# Sch3.net
KiCad netlist of a schematic drawn in Altium Designer
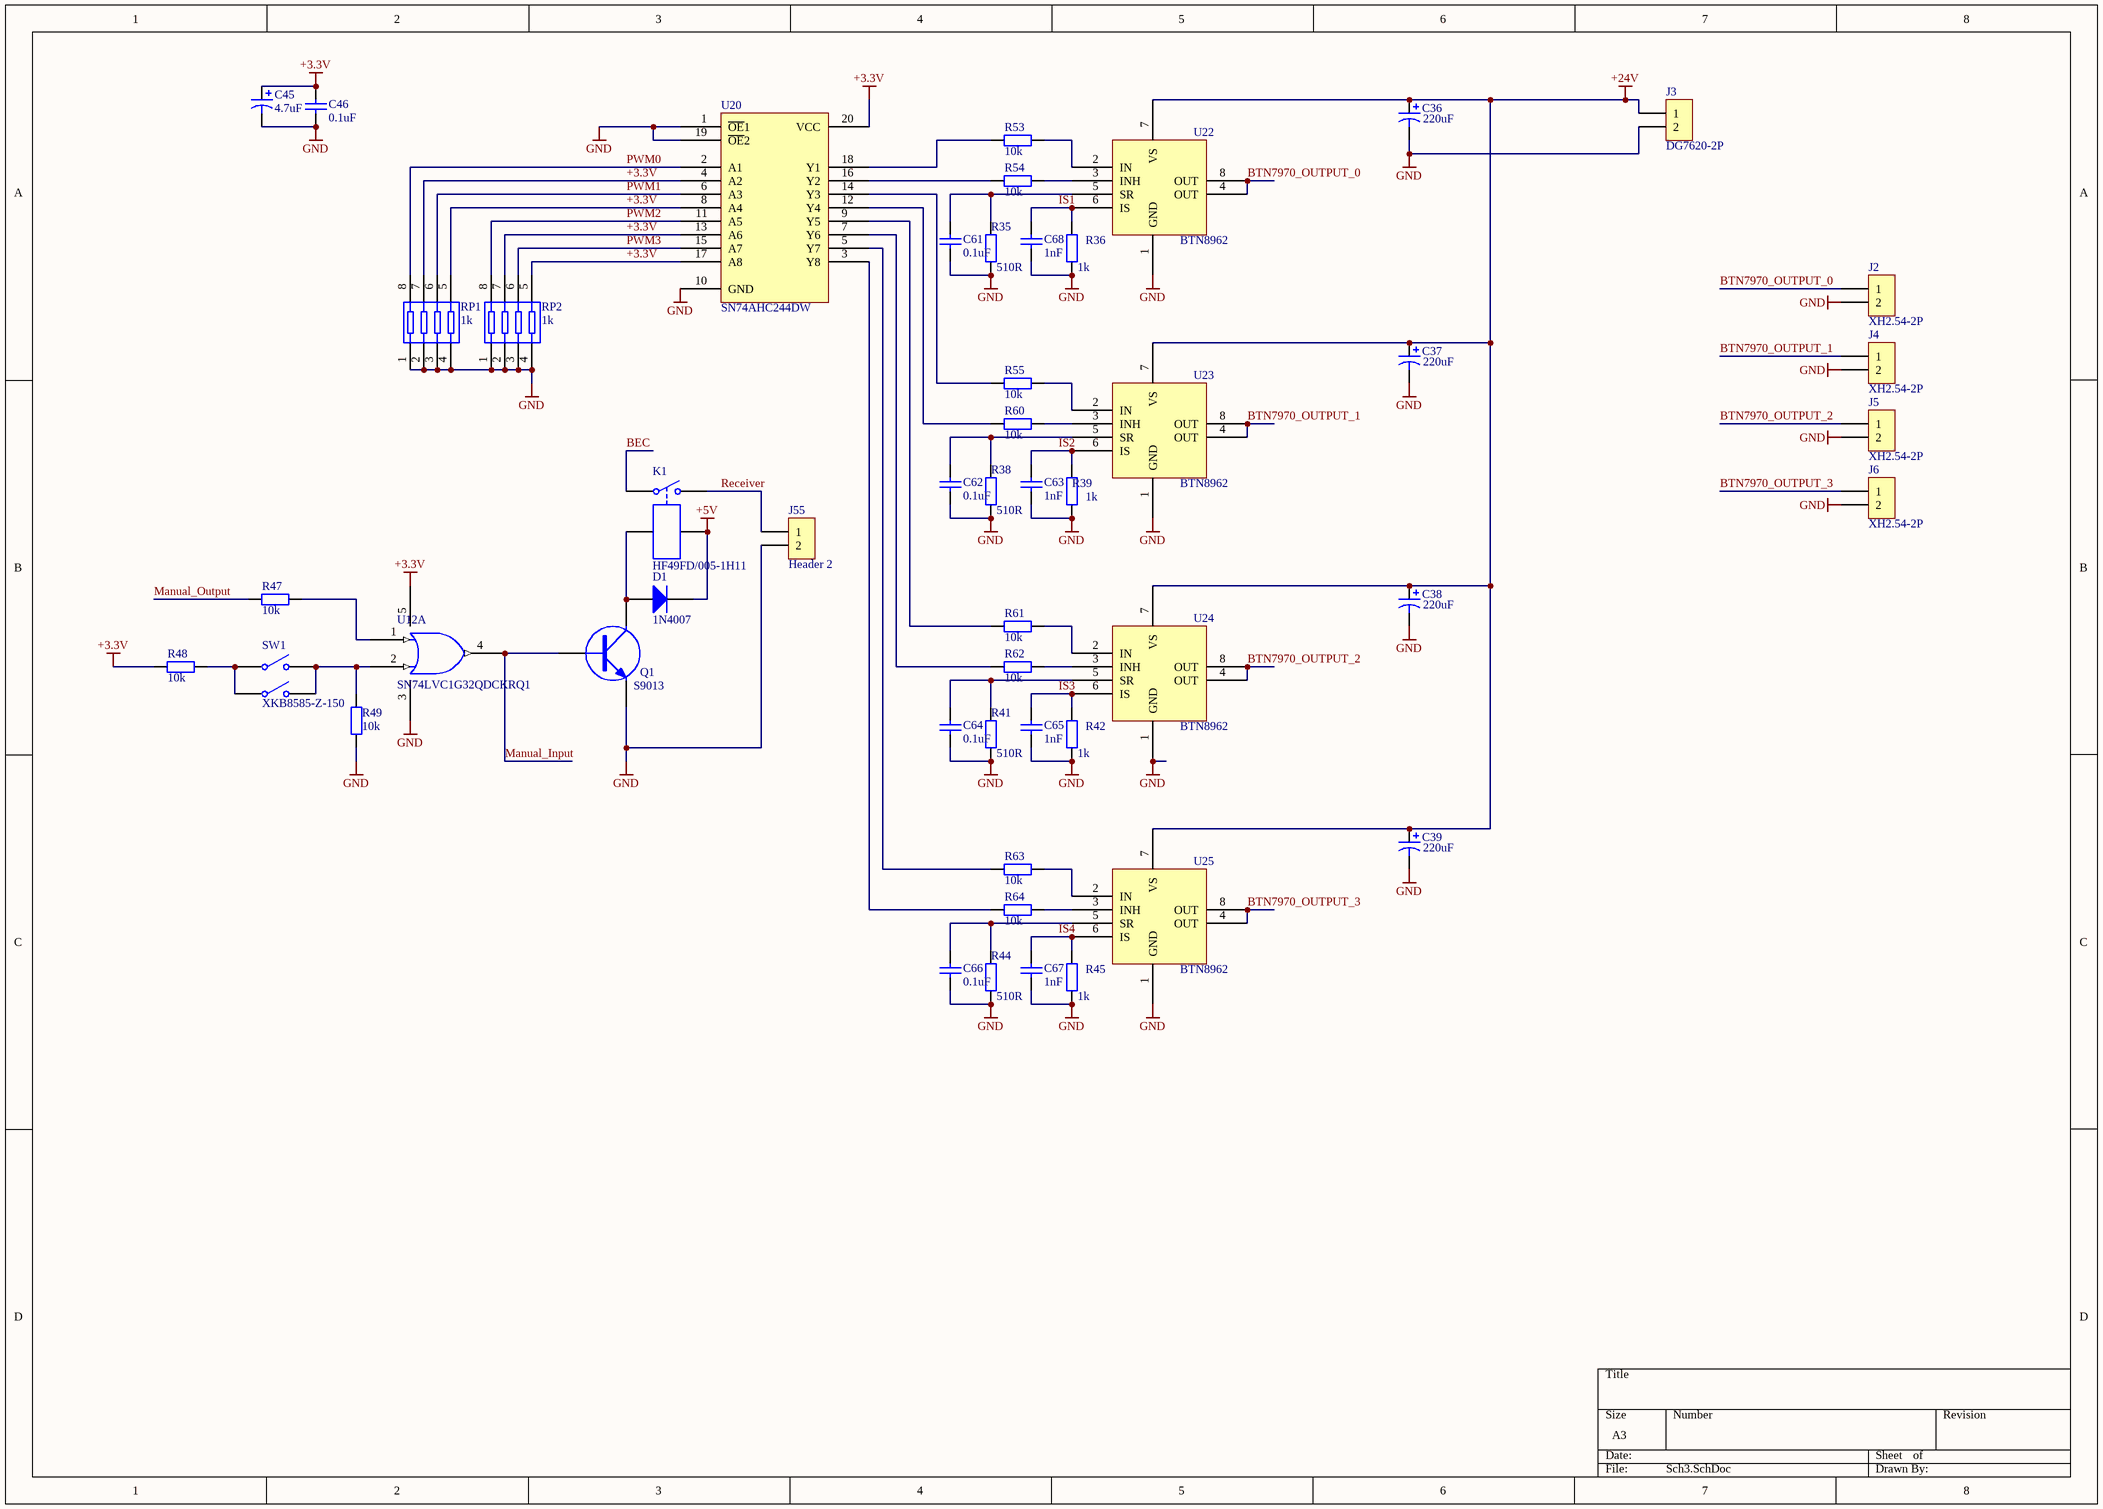
[diagram p0: Sch3.SchDoc]

(export (version "E")
  (design (tool "Eeschema 10.0.6"))
  (components
    (comp (ref "C36")
      (value "220uF")
      (footprint "SMD-EC-F8")
      (description "贴片铝电解电容")
      (fields (field (name "Comment") "CD-50V-220uF-F8(SMD)"))
      (libsource (lib "Miscellaneous Devices") (part "Cap Pol3"))
    )
    (comp (ref "C37")
      (value "220uF")
      (footprint "SMD-EC-F8")
      (description "贴片铝电解电容")
      (fields (field (name "Comment") "CD-50V-220uF-F8(SMD)"))
      (libsource (lib "Miscellaneous Devices") (part "Cap Pol3"))
    )
    (comp (ref "C38")
      (value "220uF")
      (footprint "SMD-EC-F8")
      (description "贴片铝电解电容")
      (fields (field (name "Comment") "CD-50V-220uF-F8(SMD)"))
      (libsource (lib "Miscellaneous Devices") (part "Cap Pol3"))
    )
    (comp (ref "C39")
      (value "220uF")
      (footprint "SMD-EC-F8")
      (description "贴片铝电解电容")
      (fields (field (name "Comment") "CD-50V-220uF-F8(SMD)"))
      (libsource (lib "Miscellaneous Devices") (part "Cap Pol3"))
    )
    (comp (ref "C45")
      (value "4.7uF")
      (footprint "SMD-EC-F5")
      (description "贴片铝电解电容")
      (fields (field (name "Comment") "CD-50V-4.7uF-F5(SMD)"))
      (libsource (lib "Miscellaneous Devices") (part "Cap Pol1"))
    )
    (comp (ref "C46")
      (value "0.1uF")
      (footprint "CC0603")
      (description "贴片电容")
      (fields (field (name "Comment") "0603-50V-0.1uF"))
      (libsource (lib "Miscellaneous Devices") (part "Cap"))
    )
    (comp (ref "C61")
      (value "0.1uF")
      (footprint "CC0603")
      (description "贴片电容")
      (fields (field (name "Comment") "0603-50V-0.1uF"))
      (libsource (lib "Miscellaneous Devices") (part "Cap"))
    )
    (comp (ref "C62")
      (value "0.1uF")
      (footprint "CC0603")
      (description "贴片电容")
      (fields (field (name "Comment") "0603-50V-0.1uF"))
      (libsource (lib "Miscellaneous Devices") (part "Cap"))
    )
    (comp (ref "C63")
      (value "1nF")
      (footprint "CC0603")
      (description "贴片电容")
      (fields (field (name "Comment") "0603-50V-1nF"))
      (libsource (lib "Miscellaneous Devices") (part "Cap"))
    )
    (comp (ref "C64")
      (value "0.1uF")
      (footprint "CC0603")
      (description "贴片电容")
      (fields (field (name "Comment") "0603-50V-0.1uF"))
      (libsource (lib "Miscellaneous Devices") (part "Cap"))
    )
    (comp (ref "C65")
      (value "1nF")
      (footprint "CC0603")
      (description "贴片电容")
      (fields (field (name "Comment") "0603-50V-1nF"))
      (libsource (lib "Miscellaneous Devices") (part "Cap"))
    )
    (comp (ref "C66")
      (value "0.1uF")
      (footprint "CC0603")
      (description "贴片电容")
      (fields (field (name "Comment") "0603-50V-0.1uF"))
      (libsource (lib "Miscellaneous Devices") (part "Cap"))
    )
    (comp (ref "C67")
      (value "1nF")
      (footprint "CC0603")
      (description "贴片电容")
      (fields (field (name "Comment") "0603-50V-1nF"))
      (libsource (lib "Miscellaneous Devices") (part "Cap"))
    )
    (comp (ref "C68")
      (value "1nF")
      (footprint "CC0603")
      (description "贴片电容")
      (fields (field (name "Comment") "0603-50V-1nF"))
      (libsource (lib "Miscellaneous Devices") (part "Cap"))
    )
    (comp (ref "D1")
      (value "1N4007")
      (footprint "1N4007")
      (description "贴片二极管")
      (fields (field (name "Comment") "1N4007(SOD-123FL)"))
      (libsource (lib "Miscellaneous Devices") (part "Diode"))
    )
    (comp (ref "J2")
      (value "XH2.54-2P")
      (footprint "XH2.54-2P")
      (description "插座")
      (libsource (lib "*") (part "CON2"))
    )
    (comp (ref "J3")
      (value "DG7620-2P")
      (footprint "DG7620-2P")
      (description "插座")
      (libsource (lib "*") (part "CON2"))
    )
    (comp (ref "J4")
      (value "XH2.54-2P")
      (footprint "XH2.54-2P")
      (description "插座")
      (libsource (lib "*") (part "CON2"))
    )
    (comp (ref "J5")
      (value "XH2.54-2P")
      (footprint "XH2.54-2P")
      (description "插座")
      (libsource (lib "*") (part "CON2"))
    )
    (comp (ref "J6")
      (value "XH2.54-2P")
      (footprint "XH2.54-2P")
      (description "插座")
      (libsource (lib "*") (part "CON2"))
    )
    (comp (ref "J55")
      (value "Header 2")
      (footprint "HDR1X2")
      (description "排针")
      (libsource (lib "*") (part "CON2"))
    )
    (comp (ref "K1")
      (value "HF49FD/005-1H11")
      (footprint "HF49FD")
      (description "Single-Pole Single-Throw Relay")
      (libsource (lib "Miscellaneous Devices") (part "Relay-SPST"))
    )
    (comp (ref "Q1")
      (value "S9013")
      (footprint "SOT23")
      (description "贴片三极管")
      (fields (field (name "Comment") "S9013(SOT-23)"))
      (libsource (lib "*") (part "S9013"))
    )
    (comp (ref "R35")
      (value "510R")
      (footprint "0603")
      (description "贴片电阻")
      (fields (field (name "Comment") "0603-510Ω±1％"))
      (libsource (lib "") (part "Res2_1"))
    )
    (comp (ref "R36")
      (value "1k")
      (footprint "0603")
      (description "贴片电阻")
      (fields (field (name "Comment") "0603-1kΩ±1％"))
      (libsource (lib "") (part "Res2_1"))
    )
    (comp (ref "R38")
      (value "510R")
      (footprint "0603")
      (description "贴片电阻")
      (fields (field (name "Comment") "0603-510Ω±1％"))
      (libsource (lib "") (part "Res2_1"))
    )
    (comp (ref "R39")
      (value "1k")
      (footprint "0603")
      (description "贴片电阻")
      (fields (field (name "Comment") "0603-1kΩ±1％"))
      (libsource (lib "") (part "Res2_1"))
    )
    (comp (ref "R41")
      (value "510R")
      (footprint "0603")
      (description "贴片电阻")
      (fields (field (name "Comment") "0603-510Ω±1％"))
      (libsource (lib "") (part "Res2_1"))
    )
    (comp (ref "R42")
      (value "1k")
      (footprint "0603")
      (description "贴片电阻")
      (fields (field (name "Comment") "0603-1kΩ±1％"))
      (libsource (lib "") (part "Res2_1"))
    )
    (comp (ref "R44")
      (value "510R")
      (footprint "0603")
      (description "贴片电阻")
      (fields (field (name "Comment") "0603-510Ω±1％"))
      (libsource (lib "") (part "Res2_1"))
    )
    (comp (ref "R45")
      (value "1k")
      (footprint "0603")
      (description "贴片电阻")
      (fields (field (name "Comment") "0603-1kΩ±1％"))
      (libsource (lib "") (part "Res2_1"))
    )
    (comp (ref "R47")
      (value "10k")
      (footprint "0603")
      (description "贴片电阻")
      (fields (field (name "Comment") "0603-10kΩ±1％"))
      (libsource (lib "") (part "Res2_3"))
    )
    (comp (ref "R48")
      (value "10k")
      (footprint "0603")
      (description "贴片电阻")
      (fields (field (name "Comment") "0603-10kΩ±1％"))
      (libsource (lib "") (part "Res2_3"))
    )
    (comp (ref "R49")
      (value "10k")
      (footprint "0603")
      (description "贴片电阻")
      (fields (field (name "Comment") "0603-10kΩ±1％"))
      (libsource (lib "") (part "Res2_2"))
    )
    (comp (ref "R53")
      (value "10k")
      (footprint "0603")
      (description "贴片电阻")
      (fields (field (name "Comment") "0603-10kΩ±1％"))
      (libsource (lib "Miscellaneous Devices") (part "Res2"))
    )
    (comp (ref "R54")
      (value "10k")
      (footprint "0603")
      (description "贴片电阻")
      (fields (field (name "Comment") "0603-10kΩ±1％"))
      (libsource (lib "Miscellaneous Devices") (part "Res2"))
    )
    (comp (ref "R55")
      (value "10k")
      (footprint "0603")
      (description "贴片电阻")
      (fields (field (name "Comment") "0603-10kΩ±1％"))
      (libsource (lib "Miscellaneous Devices") (part "Res2"))
    )
    (comp (ref "R60")
      (value "10k")
      (footprint "0603")
      (description "贴片电阻")
      (fields (field (name "Comment") "0603-10kΩ±1％"))
      (libsource (lib "Miscellaneous Devices") (part "Res2"))
    )
    (comp (ref "R61")
      (value "10k")
      (footprint "0603")
      (description "贴片电阻")
      (fields (field (name "Comment") "0603-10kΩ±1％"))
      (libsource (lib "Miscellaneous Devices") (part "Res2"))
    )
    (comp (ref "R62")
      (value "10k")
      (footprint "0603")
      (description "贴片电阻")
      (fields (field (name "Comment") "0603-10kΩ±1％"))
      (libsource (lib "Miscellaneous Devices") (part "Res2"))
    )
    (comp (ref "R63")
      (value "10k")
      (footprint "0603")
      (description "贴片电阻")
      (fields (field (name "Comment") "0603-10kΩ±1％"))
      (libsource (lib "Miscellaneous Devices") (part "Res2"))
    )
    (comp (ref "R64")
      (value "10k")
      (footprint "0603")
      (description "贴片电阻")
      (fields (field (name "Comment") "0603-10kΩ±1％"))
      (libsource (lib "Miscellaneous Devices") (part "Res2"))
    )
    (comp (ref "RP1")
      (value "1k")
      (footprint "RP8F")
      (description "排阻")
      (fields (field (name "Comment") "0603-1kΩ-2*4P"))
      (libsource (lib "*") (part "RESPACK8P"))
    )
    (comp (ref "RP2")
      (value "1k")
      (footprint "RP8F")
      (description "排阻")
      (fields (field (name "Comment") "0603-1kΩ-2*4P"))
      (libsource (lib "*") (part "RESPACK8P"))
    )
    (comp (ref "SW1")
      (value "XKB8585-Z-150")
      (footprint "KEY_SWITCH")
      (description "开关")
      (libsource (lib "PCB_Project") (part "SW-SPST"))
    )
    (comp (ref "U12")
      (value "SN74LVC1G32QDCKRQ1")
      (footprint "SC70-5")
      (description "集成电路")
      (libsource (lib "*") (part "74LS32"))
    )
    (comp (ref "U20")
      (value "SN74AHC244DW")
      (footprint "SOP-20")
      (description "集成电路")
      (libsource (lib "Schlib2") (part "SN74AHC244DW"))
    )
    (comp (ref "U22")
      (value "BTN8962")
      (footprint "BTN7970")
      (description "集成电路")
      (libsource (lib "Schlib2") (part "BTN8962"))
    )
    (comp (ref "U23")
      (value "BTN8962")
      (footprint "BTN7970")
      (description "集成电路")
      (libsource (lib "Schlib2") (part "BTN7970"))
    )
    (comp (ref "U24")
      (value "BTN8962")
      (footprint "BTN7970")
      (description "集成电路")
      (libsource (lib "Schlib2") (part "BTN7970"))
    )
    (comp (ref "U25")
      (value "BTN8962")
      (footprint "BTN7970")
      (description "集成电路")
      (libsource (lib "Schlib2") (part "BTN7970"))
    )
  )
  (nets
    (net (code "1") (name "+3.3V") (class "Default")
      (node (ref "C45") (pin "1") (pinfunction "1_1") (pintype "passive"))
      (node (ref "C46") (pin "2") (pinfunction "2_2") (pintype "passive"))
      (node (ref "R48") (pin "2") (pinfunction "2_2") (pintype "passive"))
      (node (ref "RP1") (pin "5") (pinfunction "5_5") (pintype "passive"))
      (node (ref "RP1") (pin "7") (pinfunction "7_7") (pintype "passive"))
      (node (ref "RP2") (pin "5") (pinfunction "5_5") (pintype "passive"))
      (node (ref "RP2") (pin "7") (pinfunction "7_7") (pintype "passive"))
      (node (ref "U12") (pin "5") (pinfunction "VCC_5") (pintype "power_in"))
      (node (ref "U20") (pin "13") (pinfunction "A6_13") (pintype "passive"))
      (node (ref "U20") (pin "17") (pinfunction "A8_17") (pintype "passive"))
      (node (ref "U20") (pin "20") (pinfunction "VCC_20") (pintype "passive"))
      (node (ref "U20") (pin "4") (pinfunction "A2_4") (pintype "passive"))
      (node (ref "U20") (pin "8") (pinfunction "A4_8") (pintype "passive"))
    )
    (net (code "2") (name "+5V") (class "Default")
      (node (ref "D1") (pin "2") (pinfunction "K_2") (pintype "passive"))
      (node (ref "K1") (pin "2") (pinfunction "4_2") (pintype "passive"))
    )
    (net (code "3") (name "+24V") (class "Default")
      (node (ref "C36") (pin "1") (pinfunction "1_1") (pintype "passive"))
      (node (ref "C37") (pin "1") (pinfunction "1_1") (pintype "passive"))
      (node (ref "C38") (pin "1") (pinfunction "1_1") (pintype "passive"))
      (node (ref "C39") (pin "1") (pinfunction "1_1") (pintype "passive"))
      (node (ref "J3") (pin "1") (pinfunction "1_1") (pintype "passive"))
      (node (ref "U22") (pin "7") (pinfunction "VS_7") (pintype "passive"))
      (node (ref "U23") (pin "7") (pinfunction "VS_7") (pintype "passive"))
      (node (ref "U24") (pin "7") (pinfunction "VS_7") (pintype "passive"))
      (node (ref "U25") (pin "7") (pinfunction "VS_7") (pintype "passive"))
    )
    (net (code "4") (name "/BEC") (class "Default")
      (node (ref "K1") (pin "3") (pinfunction "1_3") (pintype "passive"))
    )
    (net (code "5") (name "/BTN7970_OUTPUT_0") (class "Default")
      (node (ref "J2") (pin "1") (pinfunction "1_1") (pintype "passive"))
      (node (ref "U22") (pin "4") (pinfunction "OUT_4") (pintype "passive"))
      (node (ref "U22") (pin "8") (pinfunction "OUT_8") (pintype "passive"))
    )
    (net (code "6") (name "/BTN7970_OUTPUT_1") (class "Default")
      (node (ref "J4") (pin "1") (pinfunction "1_1") (pintype "passive"))
      (node (ref "U23") (pin "4") (pinfunction "OUT_4") (pintype "passive"))
      (node (ref "U23") (pin "8") (pinfunction "OUT_8") (pintype "passive"))
    )
    (net (code "7") (name "/BTN7970_OUTPUT_2") (class "Default")
      (node (ref "J5") (pin "1") (pinfunction "1_1") (pintype "passive"))
      (node (ref "U24") (pin "4") (pinfunction "OUT_4") (pintype "passive"))
      (node (ref "U24") (pin "8") (pinfunction "OUT_8") (pintype "passive"))
    )
    (net (code "8") (name "/BTN7970_OUTPUT_3") (class "Default")
      (node (ref "J6") (pin "1") (pinfunction "1_1") (pintype "passive"))
      (node (ref "U25") (pin "4") (pinfunction "OUT_4") (pintype "passive"))
      (node (ref "U25") (pin "8") (pinfunction "OUT_8") (pintype "passive"))
    )
    (net (code "9") (name "/IS1") (class "Default")
      (node (ref "C68") (pin "2") (pinfunction "2_2") (pintype "passive"))
      (node (ref "R36") (pin "2") (pinfunction "2_2") (pintype "passive"))
      (node (ref "U22") (pin "6") (pinfunction "IS_6") (pintype "passive"))
    )
    (net (code "10") (name "/IS2") (class "Default")
      (node (ref "C63") (pin "2") (pinfunction "2_2") (pintype "passive"))
      (node (ref "R39") (pin "2") (pinfunction "2_2") (pintype "passive"))
      (node (ref "U23") (pin "6") (pinfunction "IS_6") (pintype "passive"))
    )
    (net (code "11") (name "/IS3") (class "Default")
      (node (ref "C65") (pin "2") (pinfunction "2_2") (pintype "passive"))
      (node (ref "R42") (pin "2") (pinfunction "2_2") (pintype "passive"))
      (node (ref "U24") (pin "6") (pinfunction "IS_6") (pintype "passive"))
    )
    (net (code "12") (name "/IS4") (class "Default")
      (node (ref "C67") (pin "2") (pinfunction "2_2") (pintype "passive"))
      (node (ref "R45") (pin "2") (pinfunction "2_2") (pintype "passive"))
      (node (ref "U25") (pin "6") (pinfunction "IS_6") (pintype "passive"))
    )
    (net (code "13") (name "/Manual_Input") (class "Default")
      (node (ref "Q1") (pin "1") (pinfunction "B_1") (pintype "passive"))
      (node (ref "U12") (pin "4") (pintype "output"))
    )
    (net (code "14") (name "/Manual_Output") (class "Default")
      (node (ref "R47") (pin "2") (pinfunction "2_2") (pintype "passive"))
    )
    (net (code "15") (name "/PWM0") (class "Default")
      (node (ref "RP1") (pin "8") (pinfunction "8_8") (pintype "passive"))
      (node (ref "U20") (pin "2") (pinfunction "A1_2") (pintype "passive"))
    )
    (net (code "16") (name "/PWM1") (class "Default")
      (node (ref "RP1") (pin "6") (pinfunction "6_6") (pintype "passive"))
      (node (ref "U20") (pin "6") (pinfunction "A3_6") (pintype "passive"))
    )
    (net (code "17") (name "/PWM2") (class "Default")
      (node (ref "RP2") (pin "8") (pinfunction "8_8") (pintype "passive"))
      (node (ref "U20") (pin "11") (pinfunction "A5_11") (pintype "passive"))
    )
    (net (code "18") (name "/PWM3") (class "Default")
      (node (ref "RP2") (pin "6") (pinfunction "6_6") (pintype "passive"))
      (node (ref "U20") (pin "15") (pinfunction "A7_15") (pintype "passive"))
    )
    (net (code "19") (name "/Receiver") (class "Default")
      (node (ref "J55") (pin "1") (pinfunction "1_1") (pintype "passive"))
      (node (ref "K1") (pin "4") (pinfunction "2_4") (pintype "passive"))
    )
    (net (code "20") (name "GND") (class "Default")
      (node (ref "C36") (pin "2") (pinfunction "2_2") (pintype "passive"))
      (node (ref "C37") (pin "2") (pinfunction "2_2") (pintype "passive"))
      (node (ref "C38") (pin "2") (pinfunction "2_2") (pintype "passive"))
      (node (ref "C39") (pin "2") (pinfunction "2_2") (pintype "passive"))
      (node (ref "C45") (pin "2") (pinfunction "2_2") (pintype "passive"))
      (node (ref "C46") (pin "1") (pinfunction "1_1") (pintype "passive"))
      (node (ref "C61") (pin "1") (pinfunction "1_1") (pintype "passive"))
      (node (ref "C62") (pin "1") (pinfunction "1_1") (pintype "passive"))
      (node (ref "C63") (pin "1") (pinfunction "1_1") (pintype "passive"))
      (node (ref "C64") (pin "1") (pinfunction "1_1") (pintype "passive"))
      (node (ref "C65") (pin "1") (pinfunction "1_1") (pintype "passive"))
      (node (ref "C66") (pin "1") (pinfunction "1_1") (pintype "passive"))
      (node (ref "C67") (pin "1") (pinfunction "1_1") (pintype "passive"))
      (node (ref "C68") (pin "1") (pinfunction "1_1") (pintype "passive"))
      (node (ref "J2") (pin "2") (pinfunction "2_2") (pintype "passive"))
      (node (ref "J3") (pin "2") (pinfunction "2_2") (pintype "passive"))
      (node (ref "J4") (pin "2") (pinfunction "2_2") (pintype "passive"))
      (node (ref "J5") (pin "2") (pinfunction "2_2") (pintype "passive"))
      (node (ref "J55") (pin "2") (pinfunction "2_2") (pintype "passive"))
      (node (ref "J6") (pin "2") (pinfunction "2_2") (pintype "passive"))
      (node (ref "Q1") (pin "2") (pinfunction "E_2") (pintype "passive"))
      (node (ref "R35") (pin "1") (pinfunction "1_1") (pintype "passive"))
      (node (ref "R36") (pin "1") (pinfunction "1_1") (pintype "passive"))
      (node (ref "R38") (pin "1") (pinfunction "1_1") (pintype "passive"))
      (node (ref "R39") (pin "1") (pinfunction "1_1") (pintype "passive"))
      (node (ref "R41") (pin "1") (pinfunction "1_1") (pintype "passive"))
      (node (ref "R42") (pin "1") (pinfunction "1_1") (pintype "passive"))
      (node (ref "R44") (pin "1") (pinfunction "1_1") (pintype "passive"))
      (node (ref "R45") (pin "1") (pinfunction "1_1") (pintype "passive"))
      (node (ref "R49") (pin "2") (pinfunction "2_2") (pintype "passive"))
      (node (ref "RP1") (pin "1") (pinfunction "1_1") (pintype "passive"))
      (node (ref "RP1") (pin "2") (pinfunction "2_2") (pintype "passive"))
      (node (ref "RP1") (pin "3") (pinfunction "3_3") (pintype "passive"))
      (node (ref "RP1") (pin "4") (pinfunction "4_4") (pintype "passive"))
      (node (ref "RP2") (pin "1") (pinfunction "1_1") (pintype "passive"))
      (node (ref "RP2") (pin "2") (pinfunction "2_2") (pintype "passive"))
      (node (ref "RP2") (pin "3") (pinfunction "3_3") (pintype "passive"))
      (node (ref "RP2") (pin "4") (pinfunction "4_4") (pintype "passive"))
      (node (ref "U12") (pin "3") (pinfunction "GND_3") (pintype "power_in"))
      (node (ref "U20") (pin "1") (pinfunction "~{OE}1_1") (pintype "passive"))
      (node (ref "U20") (pin "10") (pinfunction "GND_10") (pintype "passive"))
      (node (ref "U20") (pin "19") (pinfunction "~{OE}2_19") (pintype "passive"))
      (node (ref "U22") (pin "1") (pinfunction "GND_1") (pintype "passive"))
      (node (ref "U23") (pin "1") (pinfunction "GND_1") (pintype "passive"))
      (node (ref "U24") (pin "1") (pinfunction "GND_1") (pintype "passive"))
      (node (ref "U25") (pin "1") (pinfunction "GND_1") (pintype "passive"))
    )
    (net (code "21") (name "Net-(D1-A)") (class "Default")
      (node (ref "D1") (pin "1") (pinfunction "A_1") (pintype "passive"))
      (node (ref "K1") (pin "1") (pinfunction "3_1") (pintype "passive"))
      (node (ref "Q1") (pin "3") (pinfunction "C_3") (pintype "passive"))
    )
    (net (code "22") (name "Net-(R47-Pad1)") (class "Default")
      (node (ref "R47") (pin "1") (pinfunction "1_1") (pintype "passive"))
      (node (ref "U12") (pin "1") (pintype "input"))
    )
    (net (code "23") (name "Net-(R48-Pad1)") (class "Default")
      (node (ref "R48") (pin "1") (pinfunction "1_1") (pintype "passive"))
      (node (ref "SW1") (pin "1") (pinfunction "COMMON_1") (pintype "passive"))
      (node (ref "SW1") (pin "6") (pinfunction "COMMON_6") (pintype "passive"))
    )
    (net (code "24") (name "Net-(R49-Pad1)") (class "Default")
      (node (ref "R49") (pin "1") (pinfunction "1_1") (pintype "passive"))
      (node (ref "SW1") (pin "2") (pinfunction "NO_2") (pintype "passive"))
      (node (ref "SW1") (pin "5") (pinfunction "NO_5") (pintype "passive"))
      (node (ref "U12") (pin "2") (pintype "input"))
    )
    (net (code "25") (name "Net-(U20-Y1)") (class "Default")
      (node (ref "R53") (pin "1") (pinfunction "1_1") (pintype "passive"))
      (node (ref "U20") (pin "18") (pinfunction "Y1_18") (pintype "passive"))
    )
    (net (code "26") (name "Net-(U20-Y2)") (class "Default")
      (node (ref "R54") (pin "1") (pinfunction "1_1") (pintype "passive"))
      (node (ref "U20") (pin "16") (pinfunction "Y2_16") (pintype "passive"))
    )
    (net (code "27") (name "Net-(U20-Y3)") (class "Default")
      (node (ref "R55") (pin "1") (pinfunction "1_1") (pintype "passive"))
      (node (ref "U20") (pin "14") (pinfunction "Y3_14") (pintype "passive"))
    )
    (net (code "28") (name "Net-(U20-Y4)") (class "Default")
      (node (ref "R60") (pin "1") (pinfunction "1_1") (pintype "passive"))
      (node (ref "U20") (pin "12") (pinfunction "Y4_12") (pintype "passive"))
    )
    (net (code "29") (name "Net-(U20-Y5)") (class "Default")
      (node (ref "R61") (pin "1") (pinfunction "1_1") (pintype "passive"))
      (node (ref "U20") (pin "9") (pinfunction "Y5_9") (pintype "passive"))
    )
    (net (code "30") (name "Net-(U20-Y6)") (class "Default")
      (node (ref "R62") (pin "1") (pinfunction "1_1") (pintype "passive"))
      (node (ref "U20") (pin "7") (pinfunction "Y6_7") (pintype "passive"))
    )
    (net (code "31") (name "Net-(U20-Y7)") (class "Default")
      (node (ref "R63") (pin "1") (pinfunction "1_1") (pintype "passive"))
      (node (ref "U20") (pin "5") (pinfunction "Y7_5") (pintype "passive"))
    )
    (net (code "32") (name "Net-(U20-Y8)") (class "Default")
      (node (ref "R64") (pin "1") (pinfunction "1_1") (pintype "passive"))
      (node (ref "U20") (pin "3") (pinfunction "Y8_3") (pintype "passive"))
    )
    (net (code "33") (name "Net-(U22-IN)") (class "Default")
      (node (ref "R53") (pin "2") (pinfunction "2_2") (pintype "passive"))
      (node (ref "U22") (pin "2") (pinfunction "IN_2") (pintype "passive"))
    )
    (net (code "34") (name "Net-(U22-INH)") (class "Default")
      (node (ref "R54") (pin "2") (pinfunction "2_2") (pintype "passive"))
      (node (ref "U22") (pin "3") (pinfunction "INH_3") (pintype "passive"))
    )
    (net (code "35") (name "Net-(U22-SR)") (class "Default")
      (node (ref "C61") (pin "2") (pinfunction "2_2") (pintype "passive"))
      (node (ref "R35") (pin "2") (pinfunction "2_2") (pintype "passive"))
      (node (ref "U22") (pin "5") (pinfunction "SR_5") (pintype "passive"))
    )
    (net (code "36") (name "Net-(U23-IN)") (class "Default")
      (node (ref "R55") (pin "2") (pinfunction "2_2") (pintype "passive"))
      (node (ref "U23") (pin "2") (pinfunction "IN_2") (pintype "passive"))
    )
    (net (code "37") (name "Net-(U23-INH)") (class "Default")
      (node (ref "R60") (pin "2") (pinfunction "2_2") (pintype "passive"))
      (node (ref "U23") (pin "3") (pinfunction "INH_3") (pintype "passive"))
    )
    (net (code "38") (name "Net-(U23-SR)") (class "Default")
      (node (ref "C62") (pin "2") (pinfunction "2_2") (pintype "passive"))
      (node (ref "R38") (pin "2") (pinfunction "2_2") (pintype "passive"))
      (node (ref "U23") (pin "5") (pinfunction "SR_5") (pintype "passive"))
    )
    (net (code "39") (name "Net-(U24-IN)") (class "Default")
      (node (ref "R61") (pin "2") (pinfunction "2_2") (pintype "passive"))
      (node (ref "U24") (pin "2") (pinfunction "IN_2") (pintype "passive"))
    )
    (net (code "40") (name "Net-(U24-INH)") (class "Default")
      (node (ref "R62") (pin "2") (pinfunction "2_2") (pintype "passive"))
      (node (ref "U24") (pin "3") (pinfunction "INH_3") (pintype "passive"))
    )
    (net (code "41") (name "Net-(U24-SR)") (class "Default")
      (node (ref "C64") (pin "2") (pinfunction "2_2") (pintype "passive"))
      (node (ref "R41") (pin "2") (pinfunction "2_2") (pintype "passive"))
      (node (ref "U24") (pin "5") (pinfunction "SR_5") (pintype "passive"))
    )
    (net (code "42") (name "Net-(U25-IN)") (class "Default")
      (node (ref "R63") (pin "2") (pinfunction "2_2") (pintype "passive"))
      (node (ref "U25") (pin "2") (pinfunction "IN_2") (pintype "passive"))
    )
    (net (code "43") (name "Net-(U25-INH)") (class "Default")
      (node (ref "R64") (pin "2") (pinfunction "2_2") (pintype "passive"))
      (node (ref "U25") (pin "3") (pinfunction "INH_3") (pintype "passive"))
    )
    (net (code "44") (name "Net-(U25-SR)") (class "Default")
      (node (ref "C66") (pin "2") (pinfunction "2_2") (pintype "passive"))
      (node (ref "R44") (pin "2") (pinfunction "2_2") (pintype "passive"))
      (node (ref "U25") (pin "5") (pinfunction "SR_5") (pintype "passive"))
    )
  )
)
